# 464342_21-005_3_3.net
KiCad netlist of a schematic drawn in Altium Designer
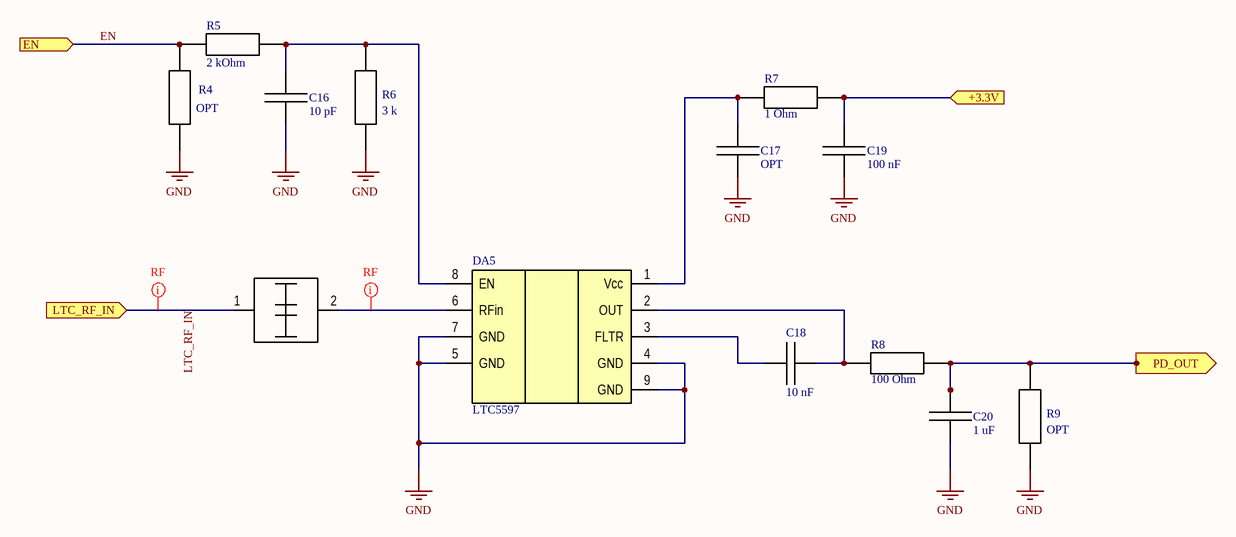
[diagram p0: МПСУ.464342.21-005 Э3 Лист3.SchDoc]

(export (version "E")
  (design (tool "Eeschema 10.0.6"))
  (components
    (comp (ref "C16")
      (value "10 pF")
      (footprint "CAPC100X50X55L20N")
      (description "Capacitor, generic")
      (libsource (lib "Discrete") (part "Capacitor"))
    )
    (comp (ref "C17")
      (value "OPT")
      (footprint "CAPC100X50X55L20N")
      (description "Capacitor, generic")
      (libsource (lib "Discrete") (part "Capacitor"))
    )
    (comp (ref "C18")
      (value "10 nF")
      (footprint "CAPC100X50X55L20N")
      (description "Capacitor, generic")
      (libsource (lib "Discrete") (part "Capacitor"))
    )
    (comp (ref "C19")
      (value "100 nF")
      (footprint "CAPC100X50X55L20N")
      (description "Capacitor, generic")
      (libsource (lib "Discrete") (part "Capacitor"))
    )
    (comp (ref "C20")
      (value "1 uF")
      (footprint "CAPC100X50X55L20N")
      (description "Capacitor, generic")
      (libsource (lib "Discrete") (part "Capacitor"))
    )
    (comp (ref "DA5")
      (value "LTC5597")
      (footprint "LTC5597")
      (description "100MHz to 70GHz Linear-in-dB RMS Power Detector with 35dB Dynamic Range")
      (fields (field (name "MANUFACTURER") "Analog Devices"))
      (libsource (lib "PowerDetectors") (part "LTC5597"))
    )
    (comp (ref "R4")
      (value "OPT")
      (footprint "RESC100X50X40L25N")
      (description "Resistor, generic")
      (libsource (lib "Discrete") (part "Resistor"))
    )
    (comp (ref "R5")
      (value "2 kOhm")
      (footprint "RESC100X50X40L25N")
      (description "Resistor, generic")
      (libsource (lib "") (part "Resistor_1"))
    )
    (comp (ref "R6")
      (value "3 k")
      (footprint "RESC100X50X40L25N")
      (description "Resistor, generic")
      (libsource (lib "Discrete") (part "Resistor"))
    )
    (comp (ref "R7")
      (value "1 Ohm")
      (footprint "RESC100X50X40L25N")
      (description "Resistor, generic")
      (libsource (lib "") (part "Resistor_1"))
    )
    (comp (ref "R8")
      (value "100 Ohm")
      (footprint "RESC100X50X40L25N")
      (description "Resistor, generic")
      (libsource (lib "") (part "Resistor_1"))
    )
    (comp (ref "R9")
      (value "OPT")
      (footprint "RESC100X50X40L25N")
      (description "Resistor, generic")
      (libsource (lib "Discrete") (part "Resistor"))
    )
    (comp (ref "W6")
      (value "Matching")
      (footprint "MATCHING_LTC_IN")
      (libsource (lib "Microstrip") (part "Matching_1"))
    )
  )
  (nets
    (net (code "1") (name "/+3.3V") (class "Default")
      (node (ref "C19") (pin "2") (pinfunction "2_2") (pintype "passive"))
      (node (ref "R7") (pin "2") (pinfunction "2_2") (pintype "passive"))
    )
    (net (code "2") (name "/EN") (class "Default")
      (node (ref "R4") (pin "2") (pinfunction "2_2") (pintype "passive"))
      (node (ref "R5") (pin "1") (pinfunction "1_1") (pintype "passive"))
    )
    (net (code "3") (name "/LTC_RF_IN") (class "Default")
      (node (ref "W6") (pin "1") (pinfunction "1_1") (pintype "passive"))
    )
    (net (code "4") (name "/PD_OUT") (class "Default")
      (node (ref "C20") (pin "2") (pinfunction "2_2") (pintype "passive"))
      (node (ref "R8") (pin "2") (pinfunction "2_2") (pintype "passive"))
      (node (ref "R9") (pin "2") (pinfunction "2_2") (pintype "passive"))
    )
    (net (code "5") (name "GND") (class "Default")
      (node (ref "C16") (pin "1") (pinfunction "1_1") (pintype "passive"))
      (node (ref "C17") (pin "1") (pinfunction "1_1") (pintype "passive"))
      (node (ref "C19") (pin "1") (pinfunction "1_1") (pintype "passive"))
      (node (ref "C20") (pin "1") (pinfunction "1_1") (pintype "passive"))
      (node (ref "DA5") (pin "4") (pinfunction "GND_4") (pintype "passive"))
      (node (ref "DA5") (pin "5") (pinfunction "GND_5") (pintype "passive"))
      (node (ref "DA5") (pin "7") (pinfunction "GND_7") (pintype "passive"))
      (node (ref "DA5") (pin "9") (pinfunction "GND_9") (pintype "passive"))
      (node (ref "R4") (pin "1") (pinfunction "1_1") (pintype "passive"))
      (node (ref "R6") (pin "1") (pinfunction "1_1") (pintype "passive"))
      (node (ref "R9") (pin "1") (pinfunction "1_1") (pintype "passive"))
    )
    (net (code "6") (name "Net-(DA5-EN)") (class "Default")
      (node (ref "C16") (pin "2") (pinfunction "2_2") (pintype "passive"))
      (node (ref "DA5") (pin "8") (pinfunction "EN_8") (pintype "passive"))
      (node (ref "R5") (pin "2") (pinfunction "2_2") (pintype "passive"))
      (node (ref "R6") (pin "2") (pinfunction "2_2") (pintype "passive"))
    )
    (net (code "7") (name "Net-(DA5-FLTR)") (class "Default")
      (node (ref "C18") (pin "1") (pinfunction "1_1") (pintype "passive"))
      (node (ref "DA5") (pin "3") (pinfunction "FLTR_3") (pintype "passive"))
    )
    (net (code "8") (name "Net-(DA5-OUT)") (class "Default")
      (node (ref "C18") (pin "2") (pinfunction "2_2") (pintype "passive"))
      (node (ref "DA5") (pin "2") (pinfunction "OUT_2") (pintype "passive"))
      (node (ref "R8") (pin "1") (pinfunction "1_1") (pintype "passive"))
    )
    (net (code "9") (name "Net-(DA5-RFin)") (class "Default")
      (node (ref "DA5") (pin "6") (pinfunction "RFin_6") (pintype "passive"))
      (node (ref "W6") (pin "2") (pinfunction "2_2") (pintype "passive"))
    )
    (net (code "10") (name "Net-(DA5-Vcc)") (class "Default")
      (node (ref "C17") (pin "2") (pinfunction "2_2") (pintype "passive"))
      (node (ref "DA5") (pin "1") (pinfunction "Vcc_1") (pintype "passive"))
      (node (ref "R7") (pin "1") (pinfunction "1_1") (pintype "passive"))
    )
  )
)
